# MC15.net
KiCad netlist of a schematic drawn in Altium Designer
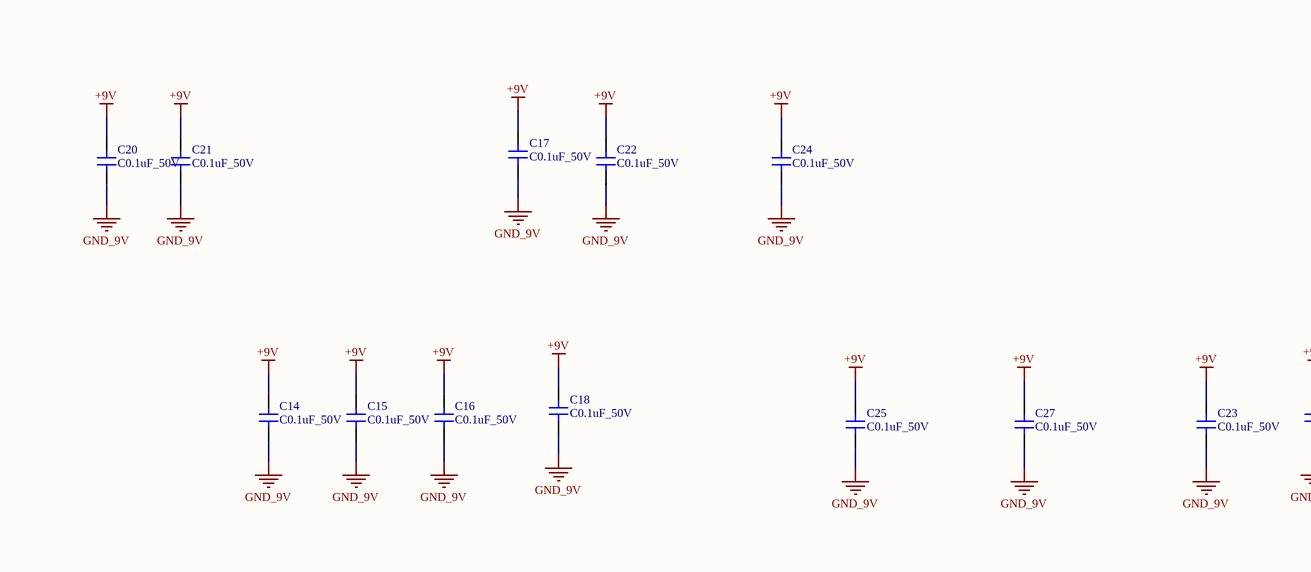
[diagram p0: MC15.SchDoc, top left]
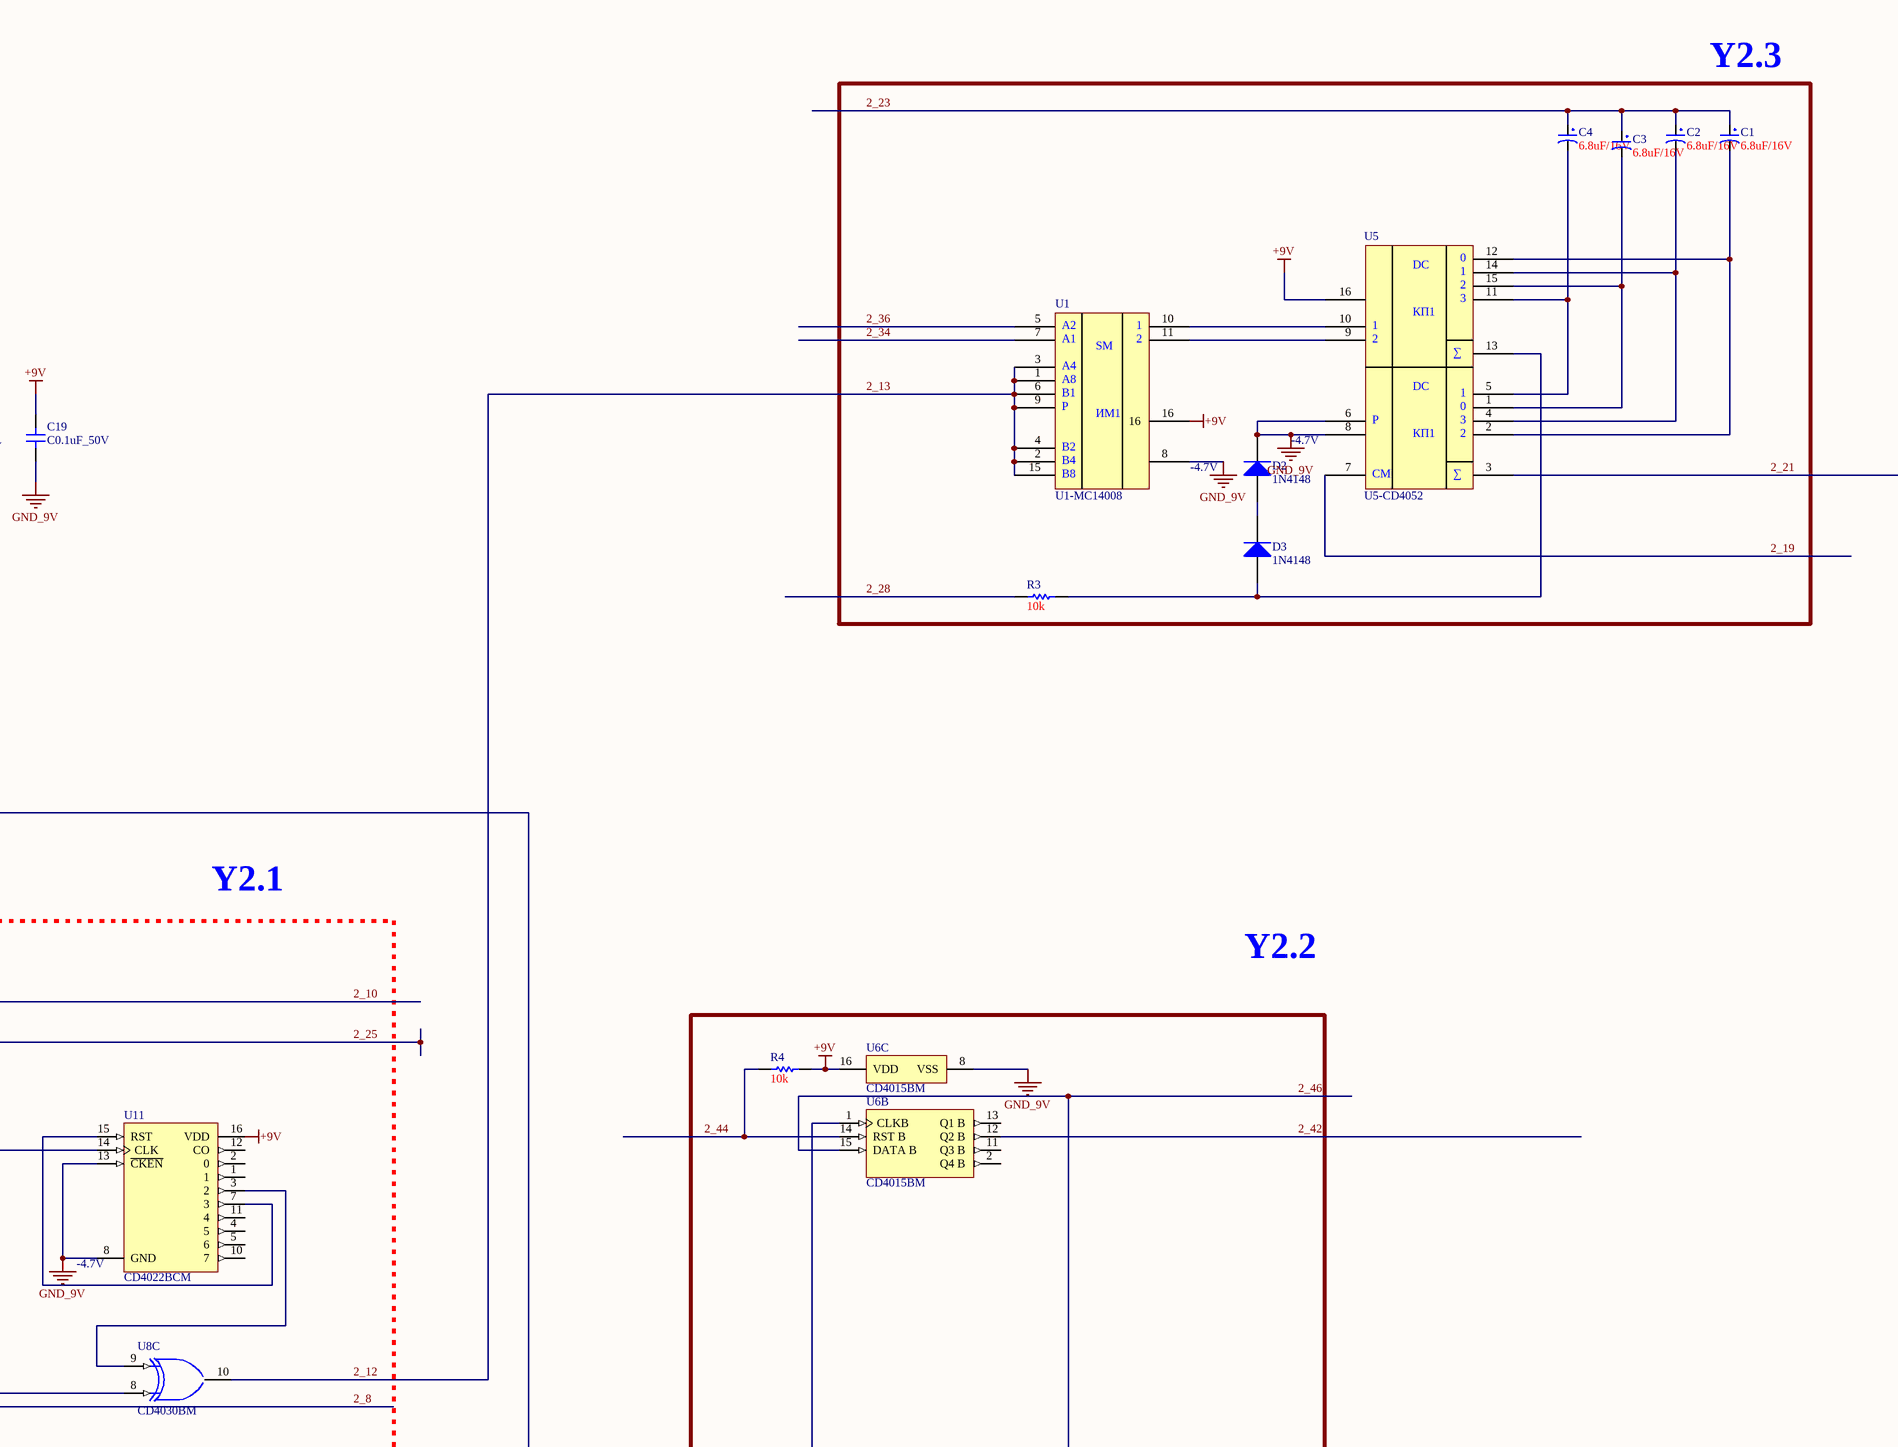
[diagram p1: MC15.SchDoc, top right]
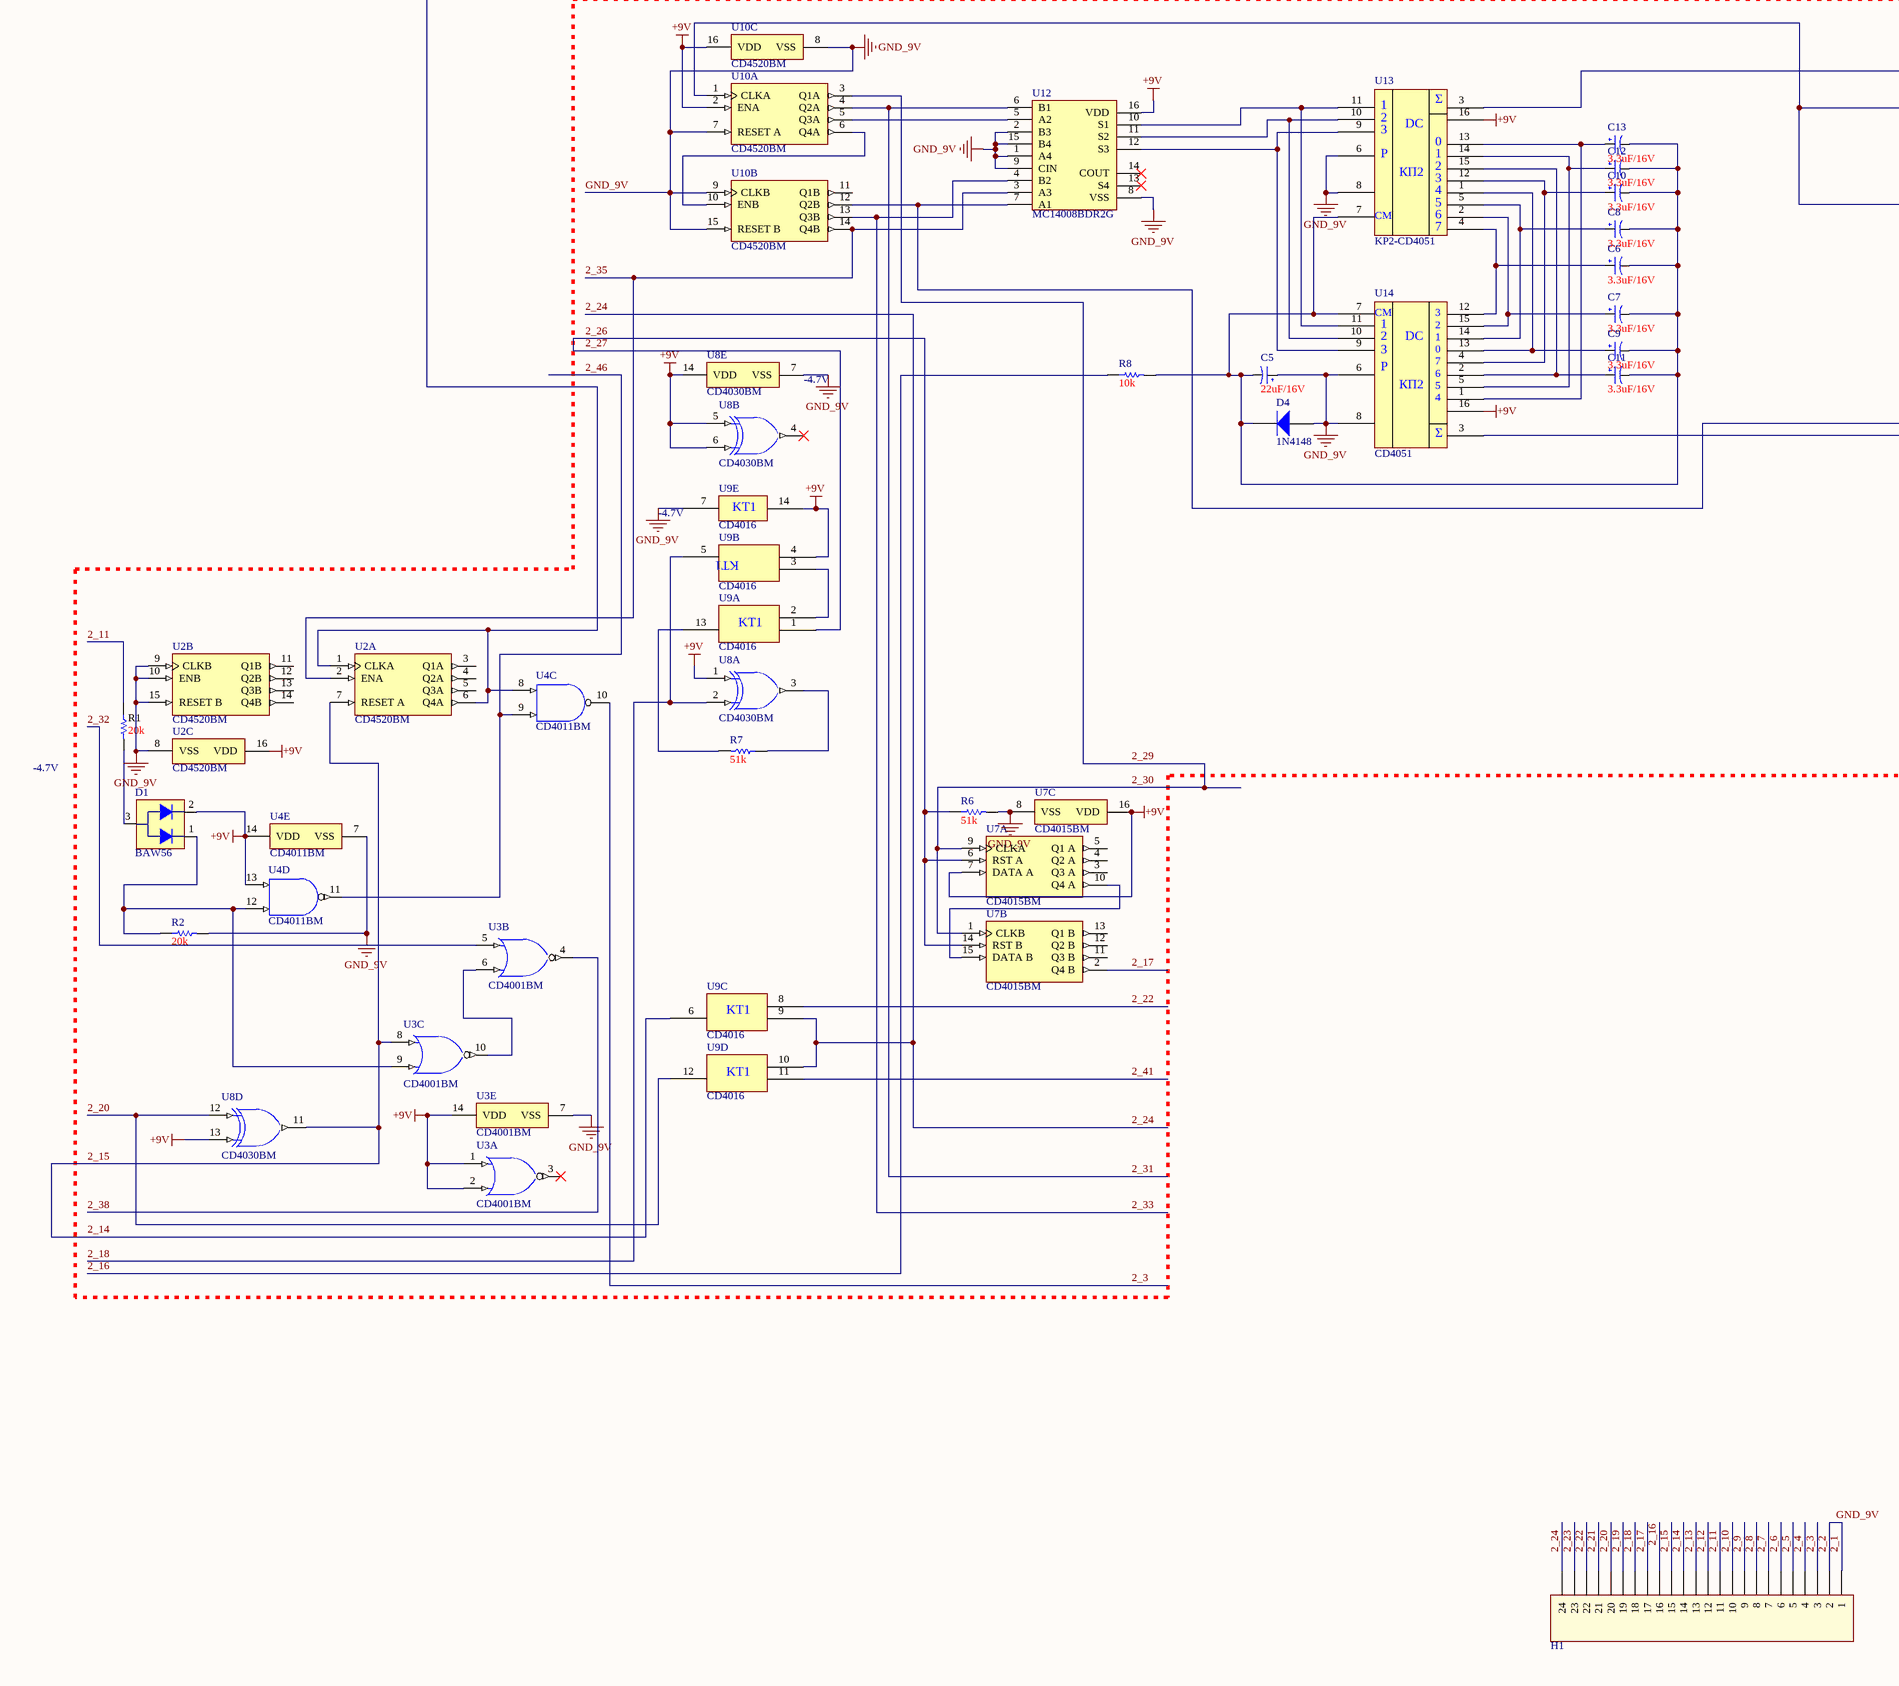
[diagram p2: MC15.SchDoc, bottom left]
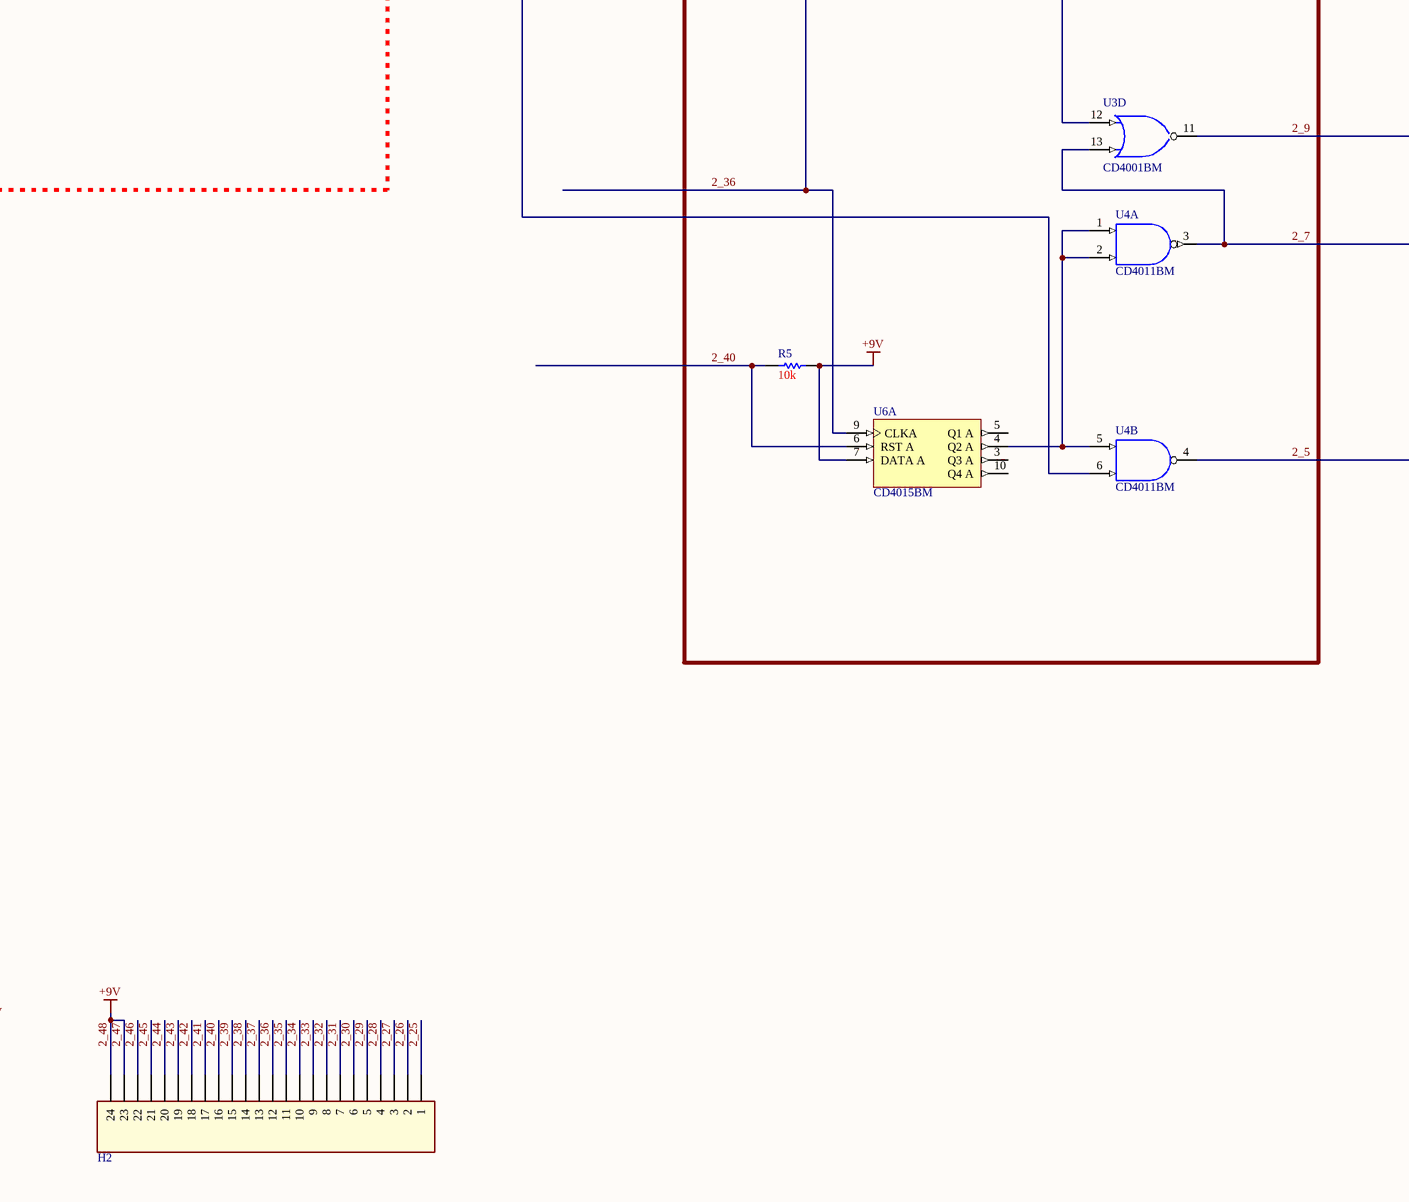
[diagram p3: MC15.SchDoc, bottom right]

(export (version "E")
  (design (tool "Eeschema 10.0.6"))
  (components
    (comp (ref "C1")
      (value "6.8uF/16V")
      (footprint "3216")
      (description "C 47uF/50V , 220uF/16V")
      (libsource (lib "syhaunguyen") (part "CP2"))
    )
    (comp (ref "C2")
      (value "6.8uF/16V")
      (footprint "3216")
      (description "C 47uF/50V , 220uF/16V")
      (libsource (lib "syhaunguyen") (part "CP2"))
    )
    (comp (ref "C3")
      (value "6.8uF/16V")
      (footprint "3216")
      (description "C 47uF/50V , 220uF/16V")
      (libsource (lib "syhaunguyen") (part "CP2"))
    )
    (comp (ref "C4")
      (value "6.8uF/16V")
      (footprint "3216")
      (description "C 47uF/50V , 220uF/16V")
      (libsource (lib "syhaunguyen") (part "CP2"))
    )
    (comp (ref "C5")
      (value "22uF/16V")
      (footprint "3528")
      (description "Cap P  0,1uF < 22uF , 16 - 50V")
      (libsource (lib "syhaunguyen") (part "CP1"))
    )
    (comp (ref "C6")
      (value "3.3uF/16V")
      (footprint "3216")
      (description "Cap P  0,1uF < 22uF , 16 - 50V")
      (libsource (lib "syhaunguyen") (part "CP1"))
    )
    (comp (ref "C7")
      (value "3.3uF/16V")
      (footprint "3216")
      (description "Cap P  0,1uF < 22uF , 16 - 50V")
      (libsource (lib "syhaunguyen") (part "CP1"))
    )
    (comp (ref "C8")
      (value "3.3uF/16V")
      (footprint "3216")
      (description "Cap P  0,1uF < 22uF , 16 - 50V")
      (libsource (lib "syhaunguyen") (part "CP1"))
    )
    (comp (ref "C9")
      (value "3.3uF/16V")
      (footprint "3216")
      (description "Cap P  0,1uF < 22uF , 16 - 50V")
      (libsource (lib "syhaunguyen") (part "CP1"))
    )
    (comp (ref "C10")
      (value "3.3uF/16V")
      (footprint "3216")
      (description "Cap P  0,1uF < 22uF , 16 - 50V")
      (libsource (lib "syhaunguyen") (part "CP1"))
    )
    (comp (ref "C11")
      (value "3.3uF/16V")
      (footprint "3216")
      (description "Cap P  0,1uF < 22uF , 16 - 50V")
      (libsource (lib "syhaunguyen") (part "CP1"))
    )
    (comp (ref "C12")
      (value "3.3uF/16V")
      (footprint "3216")
      (description "Cap P  0,1uF < 22uF , 16 - 50V")
      (libsource (lib "syhaunguyen") (part "CP1"))
    )
    (comp (ref "C13")
      (value "3.3uF/16V")
      (footprint "3216")
      (description "Cap P  0,1uF < 22uF , 16 - 50V")
      (libsource (lib "syhaunguyen") (part "CP1"))
    )
    (comp (ref "C14")
      (value "C0.1uF_50V")
      (footprint "Masterit1805:C0805")
      (libsource (lib "AMK") (part "C0.1uF_50V"))
    )
    (comp (ref "C15")
      (value "C0.1uF_50V")
      (footprint "Masterit1805:C0805")
      (libsource (lib "AMK") (part "C0.1uF_50V"))
    )
    (comp (ref "C16")
      (value "C0.1uF_50V")
      (footprint "Masterit1805:C0805")
      (libsource (lib "AMK") (part "C0.1uF_50V"))
    )
    (comp (ref "C17")
      (value "C0.1uF_50V")
      (footprint "Masterit1805:C0805")
      (libsource (lib "AMK") (part "C0.1uF_50V"))
    )
    (comp (ref "C18")
      (value "C0.1uF_50V")
      (footprint "Masterit1805:C0805")
      (libsource (lib "AMK") (part "C0.1uF_50V"))
    )
    (comp (ref "C19")
      (value "C0.1uF_50V")
      (footprint "Masterit1805:C0805")
      (libsource (lib "AMK") (part "C0.1uF_50V"))
    )
    (comp (ref "C20")
      (value "C0.1uF_50V")
      (footprint "Masterit1805:C0805")
      (libsource (lib "AMK") (part "C0.1uF_50V"))
    )
    (comp (ref "C21")
      (value "C0.1uF_50V")
      (footprint "Masterit1805:C0805")
      (libsource (lib "AMK") (part "C0.1uF_50V"))
    )
    (comp (ref "C22")
      (value "C0.1uF_50V")
      (footprint "Masterit1805:C0805")
      (libsource (lib "AMK") (part "C0.1uF_50V"))
    )
    (comp (ref "C23")
      (value "C0.1uF_50V")
      (footprint "Masterit1805:C0805")
      (libsource (lib "AMK") (part "C0.1uF_50V"))
    )
    (comp (ref "C24")
      (value "C0.1uF_50V")
      (footprint "Masterit1805:C0805")
      (libsource (lib "AMK") (part "C0.1uF_50V"))
    )
    (comp (ref "C25")
      (value "C0.1uF_50V")
      (footprint "Masterit1805:C0805")
      (libsource (lib "AMK") (part "C0.1uF_50V"))
    )
    (comp (ref "C27")
      (value "C0.1uF_50V")
      (footprint "Masterit1805:C0805")
      (libsource (lib "AMK") (part "C0.1uF_50V"))
    )
    (comp (ref "D1") (value "BAW56") (footprint "sot-23") (libsource (lib "27V-30A") (part "UF3")))
    (comp (ref "D2")
      (value "1N4148")
      (footprint "SOD123")
      (description "Dán")
      (libsource (lib "Altium_Lib_by_KhueNguyenCreator") (part "Diode S4"))
    )
    (comp (ref "D3")
      (value "1N4148")
      (footprint "SOD123")
      (description "Dán")
      (libsource (lib "Altium_Lib_by_KhueNguyenCreator") (part "Diode S4"))
    )
    (comp (ref "D4")
      (value "1N4148")
      (footprint "SOD123")
      (description "Dán")
      (libsource (lib "Altium_Lib_by_KhueNguyenCreator") (part "Diode S4"))
    )
    (comp (ref "H1")
      (value "Header 24")
      (footprint "header 24")
      (libsource (lib "LIB_EMBEDDED1805") (part "Header 24"))
    )
    (comp (ref "H2")
      (value "Header 24")
      (footprint "header 24")
      (libsource (lib "LIB_EMBEDDED1805") (part "Header 24"))
    )
    (comp (ref "R1")
      (value "20k")
      (footprint "R0805")
      (description "Standard resistor")
      (fields (field (name "ASID PART NUMBER") "Res-AS"))
      (libsource (lib "Mylib+Rev+4") (part "Res"))
    )
    (comp (ref "R2")
      (value "20k")
      (footprint "R0805")
      (description "Standard resistor")
      (fields (field (name "ASID PART NUMBER") "Res-AS"))
      (libsource (lib "Mylib+Rev+4") (part "Res"))
    )
    (comp (ref "R3")
      (value "10k")
      (footprint "Masterit1805:C0805")
      (description "Standard resistor")
      (fields (field (name "ASID PART NUMBER") "Res-AS"))
      (libsource (lib "Mylib+Rev+4") (part "Res"))
    )
    (comp (ref "R4")
      (value "10k")
      (footprint "R0805")
      (description "Standard resistor")
      (fields (field (name "ASID PART NUMBER") "Res-AS"))
      (libsource (lib "Mylib+Rev+4") (part "Res"))
    )
    (comp (ref "R5")
      (value "10k")
      (footprint "R0805")
      (description "Standard resistor")
      (fields (field (name "ASID PART NUMBER") "Res-AS"))
      (libsource (lib "Mylib+Rev+4") (part "Res"))
    )
    (comp (ref "R6")
      (value "51k")
      (footprint "R0805")
      (description "Standard resistor")
      (fields (field (name "ASID PART NUMBER") "Res-AS"))
      (libsource (lib "Mylib+Rev+4") (part "Res"))
    )
    (comp (ref "R7")
      (value "51k")
      (footprint "Masterit1805:C0805")
      (description "Standard resistor")
      (fields (field (name "ASID PART NUMBER") "Res-AS"))
      (libsource (lib "Mylib+Rev+4") (part "Res"))
    )
    (comp (ref "R8")
      (value "10k")
      (footprint "R0805")
      (description "Standard resistor")
      (fields (field (name "ASID PART NUMBER") "Res-AS"))
      (libsource (lib "Mylib+Rev+4") (part "Res"))
    )
    (comp (ref "U1")
      (value "U1-MC14008")
      (footprint "soic16n")
      (libsource (lib "LIB_OF_PHONG") (part "U1-MC14008"))
    )
    (comp (ref "U2")
      (value "CD4520BM")
      (footprint "D0016A_N")
      (description "CMOS Dual Binary Up-Counter, D0016A, TUBE")
      (fields
        (field (name "GENERIC PART NUMBER") "CD4520B")
        (field (name "MANUFACTURER") "Texas Instruments")
      )
      (libsource (lib "TI_Logic_Specialty_Logic") (part "CD4520BM"))
    )
    (comp (ref "U3")
      (value "CD4001BM")
      (footprint "D0014A_N")
      (description "CMOS Quad 2-Input NOR Gate, D0014A, TUBE")
      (fields
        (field (name "GENERIC PART NUMBER") "CD4001B")
        (field (name "MANUFACTURER") "Texas Instruments")
      )
      (libsource (lib "TI_Logic_Gate") (part "CD4001BM"))
    )
    (comp (ref "U4")
      (value "CD4011BM")
      (footprint "D0014A_N")
      (description "CMOS Quad 2-Input NAND Gate, D0014A, TUBE")
      (fields
        (field (name "GENERIC PART NUMBER") "CD4011B")
        (field (name "MANUFACTURER") "Texas Instruments")
      )
      (libsource (lib "TI_Logic_Gate") (part "CD4011BM"))
    )
    (comp (ref "U5")
      (value "U5-CD4052")
      (footprint "soic16n")
      (libsource (lib "LIB_OF_PHONG") (part "U5-CD4052"))
    )
    (comp (ref "U6")
      (value "CD4015BM")
      (footprint "D0016A_N")
      (description "CMOS Dual 4-Stage Static Shift Register, D0016A, TUBE")
      (fields
        (field (name "GENERIC PART NUMBER") "CD4015B")
        (field (name "MANUFACTURER") "Texas Instruments")
      )
      (libsource (lib "TI_Logic_Flip-Flop,Latch,Register") (part "CD4015BM"))
    )
    (comp (ref "U7")
      (value "CD4015BM")
      (footprint "D0016A_N")
      (description "CMOS Dual 4-Stage Static Shift Register, D0016A, TUBE")
      (fields
        (field (name "GENERIC PART NUMBER") "CD4015B")
        (field (name "MANUFACTURER") "Texas Instruments")
      )
      (libsource (lib "TI_Logic_Flip-Flop,Latch,Register") (part "CD4015BM"))
    )
    (comp (ref "U8")
      (value "CD4030BM")
      (footprint "D0014A_N")
      (description "CMOS Quad Exclusive-OR Gate, D0014A, TUBE")
      (fields
        (field (name "GENERIC PART NUMBER") "CD4030B")
        (field (name "MANUFACTURER") "Texas Instruments")
      )
      (libsource (lib "TI_Logic_Gate") (part "CD4030BM"))
    )
    (comp (ref "U9") (value "CD4016") (footprint "SOIC14") (libsource (lib "LIB_OF_PHONG") (part "CD4016")))
    (comp (ref "U10")
      (value "CD4520BM")
      (footprint "D0016A_N")
      (description "CMOS Dual Binary Up-Counter, D0016A, TUBE")
      (fields
        (field (name "GENERIC PART NUMBER") "CD4520B")
        (field (name "MANUFACTURER") "Texas Instruments")
      )
      (libsource (lib "TI_Logic_Specialty_Logic") (part "CD4520BM"))
    )
    (comp (ref "U11")
      (value "CD4022BCM")
      (footprint "SOP16")
      (description "Divide by 8 Counter/Divider with 8 Decoded Outputs")
      (fields (field (name "PUBLISHER") "Altium Limited"))
      (libsource (lib "FSC Logic Counter") (part "CD4022BCM"))
    )
    (comp (ref "U12")
      (value "MC14008BDR2G")
      (footprint "SamacSys:SOIC127P600X175-16N")
      (description "THAY THẾ CD4008")
      (fields (field (name "MOUSER PART NUMBER") "863-MC14008BDR2G"))
      (libsource (lib "*") (part "MC14008BDR2G"))
    )
    (comp (ref "U13")
      (value "KP2-CD4051")
      (footprint "soic16n")
      (libsource (lib "LIB_OF_PHONG") (part "KP2-CD4051"))
    )
    (comp (ref "U14") (value "CD4051") (footprint "soic16n") (libsource (lib "LIB_OF_PHONG") (part "CD4051")))
  )
  (nets
    (net (code "1") (name "+9V") (class "Default")
      (node (ref "C14") (pin "2") (pinfunction "2_2") (pintype "passive"))
      (node (ref "C15") (pin "2") (pinfunction "2_2") (pintype "passive"))
      (node (ref "C16") (pin "2") (pinfunction "2_2") (pintype "passive"))
      (node (ref "C17") (pin "2") (pinfunction "2_2") (pintype "passive"))
      (node (ref "C18") (pin "2") (pinfunction "2_2") (pintype "passive"))
      (node (ref "C19") (pin "2") (pinfunction "2_2") (pintype "passive"))
      (node (ref "C20") (pin "2") (pinfunction "2_2") (pintype "passive"))
      (node (ref "C21") (pin "2") (pinfunction "2_2") (pintype "passive"))
      (node (ref "C22") (pin "2") (pinfunction "2_2") (pintype "passive"))
      (node (ref "C23") (pin "2") (pinfunction "2_2") (pintype "passive"))
      (node (ref "C24") (pin "2") (pinfunction "2_2") (pintype "passive"))
      (node (ref "C25") (pin "2") (pinfunction "2_2") (pintype "passive"))
      (node (ref "C27") (pin "2") (pinfunction "2_2") (pintype "passive"))
      (node (ref "D1") (pin "2") (pinfunction "2_2") (pintype "passive"))
      (node (ref "H2") (pin "23") (pinfunction "23_23") (pintype "passive"))
      (node (ref "H2") (pin "24") (pinfunction "24_24") (pintype "passive"))
      (node (ref "R4") (pin "2") (pinfunction "2_2") (pintype "passive"))
      (node (ref "R5") (pin "1") (pinfunction "1_1") (pintype "passive"))
      (node (ref "U1") (pin "16") (pinfunction "16_16") (pintype "passive"))
      (node (ref "U10") (pin "16") (pinfunction "VDD_16") (pintype "power_in"))
      (node (ref "U10") (pin "2") (pinfunction "ENA_2") (pintype "input"))
      (node (ref "U11") (pin "16") (pinfunction "VDD_16") (pintype "power_in"))
      (node (ref "U12") (pin "16") (pinfunction "VDD_16") (pintype "passive"))
      (node (ref "U13") (pin "16") (pinfunction "16_16") (pintype "passive"))
      (node (ref "U14") (pin "16") (pinfunction "16_16") (pintype "passive"))
      (node (ref "U2") (pin "16") (pinfunction "VDD_16") (pintype "power_in"))
      (node (ref "U3") (pin "1") (pinfunction "A_1") (pintype "input"))
      (node (ref "U3") (pin "14") (pinfunction "VDD_14") (pintype "power_in"))
      (node (ref "U3") (pin "2") (pinfunction "B_2") (pintype "input"))
      (node (ref "U4") (pin "13") (pinfunction "H_13") (pintype "input"))
      (node (ref "U4") (pin "14") (pinfunction "VDD_14") (pintype "power_in"))
      (node (ref "U5") (pin "16") (pinfunction "16_16") (pintype "passive"))
      (node (ref "U6") (pin "16") (pinfunction "VDD_16") (pintype "power_in"))
      (node (ref "U6") (pin "7") (pinfunction "DATA_A_7") (pintype "input"))
      (node (ref "U7") (pin "16") (pinfunction "VDD_16") (pintype "power_in"))
      (node (ref "U7") (pin "7") (pinfunction "DATA_A_7") (pintype "input"))
      (node (ref "U8") (pin "1") (pinfunction "A_1") (pintype "input"))
      (node (ref "U8") (pin "13") (pinfunction "H_13") (pintype "input"))
      (node (ref "U8") (pin "14") (pinfunction "VDD_14") (pintype "power_in"))
      (node (ref "U8") (pin "5") (pinfunction "C_5") (pintype "input"))
      (node (ref "U8") (pin "6") (pinfunction "D_6") (pintype "input"))
      (node (ref "U9") (pin "14") (pinfunction "14_14") (pintype "passive"))
      (node (ref "U9") (pin "4") (pinfunction "4_4") (pintype "passive"))
    )
    (net (code "2") (name "/2_3") (class "Default")
      (node (ref "H1") (pin "3") (pinfunction "3_3") (pintype "passive"))
      (node (ref "U4") (pin "10") (pinfunction "L_10") (pintype "passive"))
    )
    (net (code "3") (name "/2_4") (class "Default")
      (node (ref "H1") (pin "4") (pinfunction "4_4") (pintype "passive"))
    )
    (net (code "4") (name "/2_5") (class "Default")
      (node (ref "H1") (pin "5") (pinfunction "5_5") (pintype "passive"))
      (node (ref "U4") (pin "4") (pinfunction "K_4") (pintype "output"))
    )
    (net (code "5") (name "/2_6") (class "Default")
      (node (ref "H1") (pin "6") (pinfunction "6_6") (pintype "passive"))
    )
    (net (code "6") (name "/2_7") (class "Default")
      (node (ref "H1") (pin "7") (pinfunction "7_7") (pintype "passive"))
      (node (ref "U3") (pin "13") (pinfunction "H_13") (pintype "input"))
      (node (ref "U4") (pin "3") (pinfunction "J_3") (pintype "output"))
    )
    (net (code "7") (name "/2_8") (class "Default")
      (node (ref "H1") (pin "8") (pinfunction "8_8") (pintype "passive"))
      (node (ref "U14") (pin "3") (pinfunction "3_3") (pintype "passive"))
    )
    (net (code "8") (name "/2_9") (class "Default")
      (node (ref "H1") (pin "9") (pinfunction "9_9") (pintype "passive"))
      (node (ref "U3") (pin "11") (pinfunction "M_11") (pintype "output"))
    )
    (net (code "9") (name "/2_10") (class "Default")
      (node (ref "H1") (pin "10") (pinfunction "10_10") (pintype "passive"))
      (node (ref "U13") (pin "3") (pinfunction "3_3") (pintype "passive"))
    )
    (net (code "10") (name "/2_11") (class "Default")
      (node (ref "H1") (pin "11") (pinfunction "11_11") (pintype "passive"))
      (node (ref "R1") (pin "1") (pinfunction "1_1") (pintype "passive"))
    )
    (net (code "11") (name "/2_12") (class "Default")
      (node (ref "H1") (pin "12") (pinfunction "12_12") (pintype "passive"))
      (node (ref "H1") (pin "13") (pinfunction "13_13") (pintype "passive"))
      (node (ref "U1") (pin "1") (pinfunction "1_1") (pintype "passive"))
      (node (ref "U1") (pin "15") (pinfunction "15_15") (pintype "passive"))
      (node (ref "U1") (pin "2") (pinfunction "2_2") (pintype "passive"))
      (node (ref "U1") (pin "3") (pinfunction "3_3") (pintype "passive"))
      (node (ref "U1") (pin "4") (pinfunction "4_4") (pintype "passive"))
      (node (ref "U1") (pin "6") (pinfunction "6_6") (pintype "passive"))
      (node (ref "U1") (pin "9") (pinfunction "9_9") (pintype "passive"))
      (node (ref "U8") (pin "10") (pinfunction "L_10") (pintype "passive"))
    )
    (net (code "12") (name "/2_14") (class "Default")
      (node (ref "H1") (pin "14") (pinfunction "14_14") (pintype "passive"))
      (node (ref "H1") (pin "15") (pinfunction "15_15") (pintype "passive"))
      (node (ref "U2") (pin "7") (pinfunction "RESET_A_7") (pintype "input"))
      (node (ref "U3") (pin "8") (pinfunction "E_8") (pintype "input"))
      (node (ref "U8") (pin "11") (pinfunction "M_11") (pintype "output"))
      (node (ref "U9") (pin "6") (pinfunction "6_6") (pintype "passive"))
    )
    (net (code "13") (name "/2_16") (class "Default")
      (node (ref "H1") (pin "16") (pinfunction "16_16") (pintype "passive"))
      (node (ref "R8") (pin "1") (pinfunction "1_1") (pintype "passive"))
    )
    (net (code "14") (name "/2_17") (class "Default")
      (node (ref "H1") (pin "17") (pinfunction "17_17") (pintype "passive"))
      (node (ref "U7") (pin "2") (pinfunction "Q4_B_2") (pintype "output"))
    )
    (net (code "15") (name "/2_18") (class "Default")
      (node (ref "H1") (pin "18") (pinfunction "18_18") (pintype "passive"))
      (node (ref "U8") (pin "2") (pinfunction "B_2") (pintype "input"))
      (node (ref "U9") (pin "5") (pinfunction "5_5") (pintype "passive"))
    )
    (net (code "16") (name "/2_19") (class "Default")
      (node (ref "H1") (pin "19") (pinfunction "19_19") (pintype "passive"))
      (node (ref "U5") (pin "7") (pinfunction "7_7") (pintype "passive"))
    )
    (net (code "17") (name "/2_20") (class "Default")
      (node (ref "H1") (pin "20") (pinfunction "20_20") (pintype "passive"))
      (node (ref "U8") (pin "12") (pinfunction "G_12") (pintype "input"))
      (node (ref "U9") (pin "12") (pinfunction "12_12") (pintype "passive"))
    )
    (net (code "18") (name "/2_21") (class "Default")
      (node (ref "H1") (pin "21") (pinfunction "21_21") (pintype "passive"))
      (node (ref "U5") (pin "3") (pinfunction "3_3") (pintype "passive"))
    )
    (net (code "19") (name "/2_22") (class "Default")
      (node (ref "H1") (pin "22") (pinfunction "22_22") (pintype "passive"))
      (node (ref "U9") (pin "8") (pinfunction "8_8") (pintype "passive"))
    )
    (net (code "20") (name "/2_23") (class "Default")
      (node (ref "C1") (pin "1") (pinfunction "1_1") (pintype "passive"))
      (node (ref "C2") (pin "1") (pinfunction "1_1") (pintype "passive"))
      (node (ref "C3") (pin "1") (pinfunction "1_1") (pintype "passive"))
      (node (ref "C4") (pin "1") (pinfunction "1_1") (pintype "passive"))
      (node (ref "H1") (pin "23") (pinfunction "23_23") (pintype "passive"))
    )
    (net (code "21") (name "/2_24") (class "Default")
      (node (ref "H1") (pin "24") (pinfunction "24_24") (pintype "passive"))
      (node (ref "U9") (pin "10") (pinfunction "10_10") (pintype "passive"))
      (node (ref "U9") (pin "9") (pinfunction "9_9") (pintype "passive"))
    )
    (net (code "22") (name "/2_25") (class "Default")
      (node (ref "H2") (pin "1") (pinfunction "1_1") (pintype "passive"))
      (node (ref "U10") (pin "1") (pinfunction "CLKA_1") (pintype "input"))
      (node (ref "U11") (pin "14") (pinfunction "CLK_14") (pintype "input"))
    )
    (net (code "23") (name "/2_26") (class "Default")
      (node (ref "H2") (pin "2") (pinfunction "2_2") (pintype "passive"))
      (node (ref "H2") (pin "3") (pinfunction "3_3") (pintype "passive"))
      (node (ref "R6") (pin "1") (pinfunction "1_1") (pintype "passive"))
      (node (ref "U7") (pin "14") (pinfunction "RST_B_14") (pintype "input"))
      (node (ref "U7") (pin "6") (pinfunction "RST_A_6") (pintype "input"))
      (node (ref "U9") (pin "1") (pinfunction "1_1") (pintype "passive"))
    )
    (net (code "24") (name "/2_28") (class "Default")
      (node (ref "H2") (pin "4") (pinfunction "4_4") (pintype "passive"))
      (node (ref "R3") (pin "2") (pinfunction "2_2") (pintype "passive"))
    )
    (net (code "25") (name "/2_29") (class "Default")
      (node (ref "H2") (pin "5") (pinfunction "5_5") (pintype "passive"))
      (node (ref "H2") (pin "6") (pinfunction "6_6") (pintype "passive"))
      (node (ref "U10") (pin "3") (pinfunction "Q1A_3") (pintype "output"))
      (node (ref "U7") (pin "1") (pinfunction "CLKB_1") (pintype "input"))
      (node (ref "U7") (pin "9") (pinfunction "CLKA_9") (pintype "input"))
    )
    (net (code "26") (name "/2_31") (class "Default")
      (node (ref "H2") (pin "7") (pinfunction "7_7") (pintype "passive"))
      (node (ref "U10") (pin "4") (pinfunction "Q2A_4") (pintype "output"))
      (node (ref "U12") (pin "6") (pinfunction "B1_6") (pintype "passive"))
    )
    (net (code "27") (name "/2_32") (class "Default")
      (node (ref "H2") (pin "8") (pinfunction "8_8") (pintype "passive"))
      (node (ref "U3") (pin "5") (pinfunction "C_5") (pintype "input"))
    )
    (net (code "28") (name "/2_33") (class "Default")
      (node (ref "H2") (pin "9") (pinfunction "9_9") (pintype "passive"))
      (node (ref "U10") (pin "13") (pinfunction "Q3B_13") (pintype "output"))
      (node (ref "U12") (pin "4") (pinfunction "B2_4") (pintype "passive"))
    )
    (net (code "29") (name "/2_34") (class "Default")
      (node (ref "H2") (pin "10") (pinfunction "10_10") (pintype "passive"))
      (node (ref "U1") (pin "7") (pinfunction "7_7") (pintype "passive"))
    )
    (net (code "30") (name "/2_35") (class "Default")
      (node (ref "H2") (pin "11") (pinfunction "11_11") (pintype "passive"))
      (node (ref "U10") (pin "14") (pinfunction "Q4B_14") (pintype "output"))
      (node (ref "U12") (pin "3") (pinfunction "A3_3") (pintype "passive"))
      (node (ref "U2") (pin "2") (pinfunction "ENA_2") (pintype "input"))
    )
    (net (code "31") (name "/2_36") (class "Default")
      (node (ref "H2") (pin "12") (pinfunction "12_12") (pintype "passive"))
      (node (ref "U1") (pin "5") (pinfunction "5_5") (pintype "passive"))
      (node (ref "U6") (pin "1") (pinfunction "CLKB_1") (pintype "input"))
      (node (ref "U6") (pin "9") (pinfunction "CLKA_9") (pintype "input"))
    )
    (net (code "32") (name "/2_37") (class "Default")
      (node (ref "H2") (pin "13") (pinfunction "13_13") (pintype "passive"))
    )
    (net (code "33") (name "/2_38") (class "Default")
      (node (ref "H2") (pin "14") (pinfunction "14_14") (pintype "passive"))
      (node (ref "U3") (pin "4") (pinfunction "K_4") (pintype "output"))
    )
    (net (code "34") (name "/2_39") (class "Default")
      (node (ref "H2") (pin "15") (pinfunction "15_15") (pintype "passive"))
    )
    (net (code "35") (name "/2_40") (class "Default")
      (node (ref "H2") (pin "16") (pinfunction "16_16") (pintype "passive"))
      (node (ref "R5") (pin "2") (pinfunction "2_2") (pintype "passive"))
      (node (ref "U6") (pin "6") (pinfunction "RST_A_6") (pintype "input"))
    )
    (net (code "36") (name "/2_41") (class "Default")
      (node (ref "H2") (pin "17") (pinfunction "17_17") (pintype "passive"))
      (node (ref "U9") (pin "11") (pinfunction "11_11") (pintype "passive"))
    )
    (net (code "37") (name "/2_42") (class "Default")
      (node (ref "H2") (pin "18") (pinfunction "18_18") (pintype "passive"))
      (node (ref "U6") (pin "12") (pinfunction "Q2_B_12") (pintype "output"))
    )
    (net (code "38") (name "/2_43") (class "Default")
      (node (ref "H2") (pin "19") (pinfunction "19_19") (pintype "passive"))
    )
    (net (code "39") (name "/2_44") (class "Default")
      (node (ref "H2") (pin "20") (pinfunction "20_20") (pintype "passive"))
      (node (ref "R4") (pin "1") (pinfunction "1_1") (pintype "passive"))
      (node (ref "U6") (pin "14") (pinfunction "RST_B_14") (pintype "input"))
    )
    (net (code "40") (name "/2_45") (class "Default")
      (node (ref "H2") (pin "21") (pinfunction "21_21") (pintype "passive"))
    )
    (net (code "41") (name "/2_46") (class "Default")
      (node (ref "H2") (pin "22") (pinfunction "22_22") (pintype "passive"))
      (node (ref "U3") (pin "12") (pinfunction "G_12") (pintype "input"))
      (node (ref "U4") (pin "11") (pinfunction "M_11") (pintype "output"))
      (node (ref "U4") (pin "9") (pinfunction "F_9") (pintype "input"))
      (node (ref "U6") (pin "15") (pinfunction "DATA_B_15") (pintype "input"))
    )
    (net (code "42") (name "GND_9V") (class "Default")
      (node (ref "C14") (pin "1") (pinfunction "1_1") (pintype "passive"))
      (node (ref "C15") (pin "1") (pinfunction "1_1") (pintype "passive"))
      (node (ref "C16") (pin "1") (pinfunction "1_1") (pintype "passive"))
      (node (ref "C17") (pin "1") (pinfunction "1_1") (pintype "passive"))
      (node (ref "C18") (pin "1") (pinfunction "1_1") (pintype "passive"))
      (node (ref "C19") (pin "1") (pinfunction "1_1") (pintype "passive"))
      (node (ref "C20") (pin "1") (pinfunction "1_1") (pintype "passive"))
      (node (ref "C21") (pin "1") (pinfunction "1_1") (pintype "passive"))
      (node (ref "C22") (pin "1") (pinfunction "1_1") (pintype "passive"))
      (node (ref "C23") (pin "1") (pinfunction "1_1") (pintype "passive"))
      (node (ref "C24") (pin "1") (pinfunction "1_1") (pintype "passive"))
      (node (ref "C25") (pin "1") (pinfunction "1_1") (pintype "passive"))
      (node (ref "C27") (pin "1") (pinfunction "1_1") (pintype "passive"))
      (node (ref "C5") (pin "1") (pinfunction "1_1") (pintype "passive"))
      (node (ref "D2") (pin "2") (pinfunction "K_2") (pintype "passive"))
      (node (ref "D4") (pin "1") (pinfunction "A_1") (pintype "passive"))
      (node (ref "H1") (pin "1") (pinfunction "1_1") (pintype "passive"))
      (node (ref "H1") (pin "2") (pinfunction "2_2") (pintype "passive"))
      (node (ref "R2") (pin "2") (pinfunction "2_2") (pintype "passive"))
      (node (ref "R6") (pin "2") (pinfunction "2_2") (pintype "passive"))
      (node (ref "U1") (pin "8") (pinfunction "8_8") (pintype "passive"))
      (node (ref "U10") (pin "15") (pinfunction "RESET_B_15") (pintype "input"))
      (node (ref "U10") (pin "7") (pinfunction "RESET_A_7") (pintype "input"))
      (node (ref "U10") (pin "8") (pinfunction "VSS_8") (pintype "power_in"))
      (node (ref "U10") (pin "9") (pinfunction "CLKB_9") (pintype "input"))
      (node (ref "U11") (pin "13") (pinfunction "~{CKEN}_13") (pintype "input"))
      (node (ref "U11") (pin "8") (pinfunction "GND_8") (pintype "power_in"))
      (node (ref "U12") (pin "1") (pinfunction "A4_1") (pintype "passive"))
      (node (ref "U12") (pin "15") (pinfunction "B4_15") (pintype "passive"))
      (node (ref "U12") (pin "2") (pinfunction "B3_2") (pintype "passive"))
      (node (ref "U12") (pin "8") (pinfunction "VSS_8") (pintype "passive"))
      (node (ref "U12") (pin "9") (pinfunction "CIN_9") (pintype "passive"))
      (node (ref "U13") (pin "6") (pinfunction "6_6") (pintype "passive"))
      (node (ref "U13") (pin "8") (pinfunction "8_8") (pintype "passive"))
      (node (ref "U14") (pin "6") (pinfunction "6_6") (pintype "passive"))
      (node (ref "U14") (pin "8") (pinfunction "8_8") (pintype "passive"))
      (node (ref "U2") (pin "10") (pinfunction "ENB_10") (pintype "input"))
      (node (ref "U2") (pin "15") (pinfunction "RESET_B_15") (pintype "input"))
      (node (ref "U2") (pin "8") (pinfunction "VSS_8") (pintype "power_in"))
      (node (ref "U2") (pin "9") (pinfunction "CLKB_9") (pintype "input"))
      (node (ref "U3") (pin "7") (pinfunction "VSS_7") (pintype "power_in"))
      (node (ref "U4") (pin "7") (pinfunction "VSS_7") (pintype "power_in"))
      (node (ref "U5") (pin "6") (pinfunction "6_6") (pintype "passive"))
      (node (ref "U5") (pin "8") (pinfunction "8_8") (pintype "passive"))
      (node (ref "U6") (pin "8") (pinfunction "VSS_8") (pintype "power_in"))
      (node (ref "U7") (pin "8") (pinfunction "VSS_8") (pintype "power_in"))
      (node (ref "U8") (pin "7") (pinfunction "VSS_7") (pintype "power_in"))
      (node (ref "U9") (pin "7") (pinfunction "7_7") (pintype "passive"))
    )
    (net (code "43") (name "Net-(C1-Pad2)") (class "Default")
      (node (ref "C1") (pin "2") (pinfunction "2_2") (pintype "passive"))
      (node (ref "U5") (pin "12") (pinfunction "12_12") (pintype "passive"))
      (node (ref "U5") (pin "2") (pinfunction "2_2") (pintype "passive"))
    )
    (net (code "44") (name "Net-(C2-Pad2)") (class "Default")
      (node (ref "C2") (pin "2") (pinfunction "2_2") (pintype "passive"))
      (node (ref "U5") (pin "14") (pinfunction "14_14") (pintype "passive"))
      (node (ref "U5") (pin "4") (pinfunction "4_4") (pintype "passive"))
    )
    (net (code "45") (name "Net-(C3-Pad2)") (class "Default")
      (node (ref "C3") (pin "2") (pinfunction "2_2") (pintype "passive"))
      (node (ref "U5") (pin "1") (pinfunction "1_1") (pintype "passive"))
      (node (ref "U5") (pin "15") (pinfunction "15_15") (pintype "passive"))
    )
    (net (code "46") (name "Net-(C4-Pad2)") (class "Default")
      (node (ref "C4") (pin "2") (pinfunction "2_2") (pintype "passive"))
      (node (ref "U5") (pin "11") (pinfunction "11_11") (pintype "passive"))
      (node (ref "U5") (pin "5") (pinfunction "5_5") (pintype "passive"))
    )
    (net (code "47") (name "Net-(C6-Pad1)") (class "Default")
      (node (ref "C6") (pin "1") (pinfunction "1_1") (pintype "passive"))
      (node (ref "U13") (pin "4") (pinfunction "4_4") (pintype "passive"))
      (node (ref "U14") (pin "12") (pinfunction "12_12") (pintype "passive"))
    )
    (net (code "48") (name "Net-(C7-Pad1)") (class "Default")
      (node (ref "C7") (pin "1") (pinfunction "1_1") (pintype "passive"))
      (node (ref "U13") (pin "2") (pinfunction "2_2") (pintype "passive"))
      (node (ref "U14") (pin "15") (pinfunction "15_15") (pintype "passive"))
    )
    (net (code "49") (name "Net-(C8-Pad1)") (class "Default")
      (node (ref "C8") (pin "1") (pinfunction "1_1") (pintype "passive"))
      (node (ref "U13") (pin "5") (pinfunction "5_5") (pintype "passive"))
      (node (ref "U14") (pin "14") (pinfunction "14_14") (pintype "passive"))
    )
    (net (code "50") (name "Net-(C9-Pad1)") (class "Default")
      (node (ref "C9") (pin "1") (pinfunction "1_1") (pintype "passive"))
      (node (ref "U13") (pin "1") (pinfunction "1_1") (pintype "passive"))
      (node (ref "U14") (pin "13") (pinfunction "13_13") (pintype "passive"))
    )
    (net (code "51") (name "Net-(C10-Pad1)") (class "Default")
      (node (ref "C10") (pin "1") (pinfunction "1_1") (pintype "passive"))
      (node (ref "U13") (pin "12") (pinfunction "12_12") (pintype "passive"))
      (node (ref "U14") (pin "4") (pinfunction "4_4") (pintype "passive"))
    )
    (net (code "52") (name "Net-(C11-Pad1)") (class "Default")
      (node (ref "C11") (pin "1") (pinfunction "1_1") (pintype "passive"))
      (node (ref "U13") (pin "15") (pinfunction "15_15") (pintype "passive"))
      (node (ref "U14") (pin "2") (pinfunction "2_2") (pintype "passive"))
    )
    (net (code "53") (name "Net-(C12-Pad1)") (class "Default")
      (node (ref "C12") (pin "1") (pinfunction "1_1") (pintype "passive"))
      (node (ref "U13") (pin "14") (pinfunction "14_14") (pintype "passive"))
      (node (ref "U14") (pin "5") (pinfunction "5_5") (pintype "passive"))
    )
    (net (code "54") (name "Net-(C13-Pad1)") (class "Default")
      (node (ref "C13") (pin "1") (pinfunction "1_1") (pintype "passive"))
      (node (ref "U13") (pin "13") (pinfunction "13_13") (pintype "passive"))
      (node (ref "U14") (pin "1") (pinfunction "1_1") (pintype "passive"))
    )
    (net (code "55") (name "Net-(D1-Pad3)") (class "Default")
      (node (ref "D1") (pin "3") (pinfunction "3_3") (pintype "passive"))
      (node (ref "R1") (pin "2") (pinfunction "2_2") (pintype "passive"))
    )
    (net (code "56") (name "Net-(D2-A)") (class "Default")
      (node (ref "D2") (pin "1") (pinfunction "A_1") (pintype "passive"))
      (node (ref "D3") (pin "2") (pinfunction "K_2") (pintype "passive"))
    )
    (net (code "57") (name "Net-(D3-A)") (class "Default")
      (node (ref "D3") (pin "1") (pinfunction "A_1") (pintype "passive"))
      (node (ref "R3") (pin "1") (pinfunction "1_1") (pintype "passive"))
      (node (ref "U5") (pin "13") (pinfunction "13_13") (pintype "passive"))
    )
    (net (code "58") (name "Net-(D4-K)") (class "Default")
      (node (ref "C10") (pin "2") (pinfunction "2_2") (pintype "passive"))
      (node (ref "C11") (pin "2") (pinfunction "2_2") (pintype "passive"))
      (node (ref "C12") (pin "2") (pinfunction "2_2") (pintype "passive"))
      (node (ref "C13") (pin "2") (pinfunction "2_2") (pintype "passive"))
      (node (ref "C5") (pin "2") (pinfunction "2_2") (pintype "passive"))
      (node (ref "C6") (pin "2") (pinfunction "2_2") (pintype "passive"))
      (node (ref "C7") (pin "2") (pinfunction "2_2") (pintype "passive"))
      (node (ref "C8") (pin "2") (pinfunction "2_2") (pintype "passive"))
      (node (ref "C9") (pin "2") (pinfunction "2_2") (pintype "passive"))
      (node (ref "D4") (pin "2") (pinfunction "K_2") (pintype "passive"))
      (node (ref "R8") (pin "2") (pinfunction "2_2") (pintype "passive"))
      (node (ref "U13") (pin "7") (pinfunction "7_7") (pintype "passive"))
      (node (ref "U14") (pin "7") (pinfunction "7_7") (pintype "passive"))
    )
    (net (code "59") (name "Net-(R7-Pad2)") (class "Default")
      (node (ref "R7") (pin "2") (pinfunction "2_2") (pintype "passive"))
      (node (ref "U9") (pin "13") (pinfunction "13_13") (pintype "passive"))
    )
    (net (code "60") (name "Net-(U1-Pad10)") (class "Default")
      (node (ref "U1") (pin "10") (pinfunction "10_10") (pintype "passive"))
      (node (ref "U5") (pin "10") (pinfunction "10_10") (pintype "passive"))
    )
    (net (code "61") (name "Net-(U1-Pad11)") (class "Default")
      (node (ref "U1") (pin "11") (pinfunction "11_11") (pintype "passive"))
      (node (ref "U5") (pin "9") (pinfunction "9_9") (pintype "passive"))
    )
    (net (code "62") (name "Net-(U2A-CLKA)") (class "Default")
      (node (ref "U2") (pin "1") (pinfunction "CLKA_1") (pintype "input"))
      (node (ref "U2") (pin "6") (pinfunction "Q4A_6") (pintype "output"))
      (node (ref "U4") (pin "6") (pinfunction "D_6") (pintype "input"))
      (node (ref "U4") (pin "8") (pinfunction "E_8") (pintype "input"))
    )
    (net (code "63") (name "Net-(U3B-D)") (class "Default")
      (node (ref "U3") (pin "10") (pinfunction "L_10") (pintype "output"))
      (node (ref "U3") (pin "6") (pinfunction "D_6") (pintype "input"))
    )
    (net (code "64") (name "Net-(U3C-F)") (class "Default")
      (node (ref "D1") (pin "1") (pinfunction "1_1") (pintype "passive"))
      (node (ref "R2") (pin "1") (pinfunction "1_1") (pintype "passive"))
      (node (ref "U3") (pin "9") (pinfunction "F_9") (pintype "input"))
      (node (ref "U4") (pin "12") (pinfunction "G_12") (pintype "input"))
    )
    (net (code "65") (name "Net-(U4A-A)") (class "Default")
      (node (ref "U4") (pin "1") (pinfunction "A_1") (pintype "input"))
      (node (ref "U4") (pin "2") (pinfunction "B_2") (pintype "input"))
      (node (ref "U4") (pin "5") (pinfunction "C_5") (pintype "input"))
      (node (ref "U6") (pin "4") (pinfunction "Q2_A_4") (pintype "output"))
    )
    (net (code "66") (name "Net-(U7A-Q4_A)") (class "Default")
      (node (ref "U7") (pin "10") (pinfunction "Q4_A_10") (pintype "output"))
      (node (ref "U7") (pin "15") (pinfunction "DATA_B_15") (pintype "input"))
    )
    (net (code "67") (name "Net-(U8A-J)") (class "Default")
      (node (ref "R7") (pin "1") (pinfunction "1_1") (pintype "passive"))
      (node (ref "U8") (pin "3") (pinfunction "J_3") (pintype "output"))
    )
    (net (code "68") (name "Net-(U9-Pad2)") (class "Default")
      (node (ref "U9") (pin "2") (pinfunction "2_2") (pintype "passive"))
      (node (ref "U9") (pin "3") (pinfunction "3_3") (pintype "passive"))
    )
    (net (code "69") (name "Net-(U10A-Q3A)") (class "Default")
      (node (ref "U10") (pin "5") (pinfunction "Q3A_5") (pintype "output"))
      (node (ref "U12") (pin "5") (pinfunction "A2_5") (pintype "passive"))
    )
    (net (code "70") (name "Net-(U10A-Q4A)") (class "Default")
      (node (ref "U10") (pin "10") (pinfunction "ENB_10") (pintype "input"))
      (node (ref "U10") (pin "6") (pinfunction "Q4A_6") (pintype "output"))
    )
    (net (code "71") (name "Net-(U10B-Q2B)") (class "Default")
      (node (ref "U10") (pin "12") (pinfunction "Q2B_12") (pintype "output"))
      (node (ref "U12") (pin "7") (pinfunction "A1_7") (pintype "passive"))
      (node (ref "U8") (pin "8") (pinfunction "E_8") (pintype "input"))
    )
    (net (code "72") (name "Net-(U11-2)") (class "Default")
      (node (ref "U11") (pin "3") (pinfunction "2_3") (pintype "output"))
      (node (ref "U8") (pin "9") (pinfunction "F_9") (pintype "input"))
    )
    (net (code "73") (name "Net-(U11-3)") (class "Default")
      (node (ref "U11") (pin "15") (pinfunction "RST_15") (pintype "input"))
      (node (ref "U11") (pin "7") (pinfunction "3_7") (pintype "output"))
    )
    (net (code "74") (name "Net-(U12-S1)") (class "Default")
      (node (ref "U12") (pin "10") (pinfunction "S1_10") (pintype "passive"))
      (node (ref "U13") (pin "11") (pinfunction "11_11") (pintype "passive"))
      (node (ref "U14") (pin "11") (pinfunction "11_11") (pintype "passive"))
    )
    (net (code "75") (name "Net-(U12-S2)") (class "Default")
      (node (ref "U12") (pin "11") (pinfunction "S2_11") (pintype "passive"))
      (node (ref "U13") (pin "10") (pinfunction "10_10") (pintype "passive"))
      (node (ref "U14") (pin "10") (pinfunction "10_10") (pintype "passive"))
    )
    (net (code "76") (name "Net-(U12-S3)") (class "Default")
      (node (ref "U12") (pin "12") (pinfunction "S3_12") (pintype "passive"))
      (node (ref "U13") (pin "9") (pinfunction "9_9") (pintype "passive"))
      (node (ref "U14") (pin "9") (pinfunction "9_9") (pintype "passive"))
    )
    (net (code "77") (name "unconnected-(U2A-Q1A-Pad3)") (class "Default")
      (node (ref "U2") (pin "3") (pinfunction "Q1A_3") (pintype "output"))
    )
    (net (code "78") (name "unconnected-(U2A-Q2A-Pad4)") (class "Default")
      (node (ref "U2") (pin "4") (pinfunction "Q2A_4") (pintype "output"))
    )
    (net (code "79") (name "unconnected-(U2A-Q3A-Pad5)") (class "Default")
      (node (ref "U2") (pin "5") (pinfunction "Q3A_5") (pintype "output"))
    )
    (net (code "80") (name "unconnected-(U2B-Q1B-Pad11)") (class "Default")
      (node (ref "U2") (pin "11") (pinfunction "Q1B_11") (pintype "output"))
    )
    (net (code "81") (name "unconnected-(U2B-Q2B-Pad12)") (class "Default")
      (node (ref "U2") (pin "12") (pinfunction "Q2B_12") (pintype "output"))
    )
    (net (code "82") (name "unconnected-(U2B-Q3B-Pad13)") (class "Default")
      (node (ref "U2") (pin "13") (pinfunction "Q3B_13") (pintype "output"))
    )
    (net (code "83") (name "unconnected-(U2B-Q4B-Pad14)") (class "Default")
      (node (ref "U2") (pin "14") (pinfunction "Q4B_14") (pintype "output"))
    )
    (net (code "84") (name "unconnected-(U3A-J-Pad3)") (class "Default")
      (node (ref "U3") (pin "3") (pinfunction "J_3") (pintype "output+no_connect"))
    )
    (net (code "85") (name "unconnected-(U6A-Q1_A-Pad5)") (class "Default")
      (node (ref "U6") (pin "5") (pinfunction "Q1_A_5") (pintype "output"))
    )
    (net (code "86") (name "unconnected-(U6A-Q3_A-Pad3)") (class "Default")
      (node (ref "U6") (pin "3") (pinfunction "Q3_A_3") (pintype "output"))
    )
    (net (code "87") (name "unconnected-(U6A-Q4_A-Pad10)") (class "Default")
      (node (ref "U6") (pin "10") (pinfunction "Q4_A_10") (pintype "output"))
    )
    (net (code "88") (name "unconnected-(U6B-Q1_B-Pad13)") (class "Default")
      (node (ref "U6") (pin "13") (pinfunction "Q1_B_13") (pintype "output"))
    )
    (net (code "89") (name "unconnected-(U6B-Q3_B-Pad11)") (class "Default")
      (node (ref "U6") (pin "11") (pinfunction "Q3_B_11") (pintype "output"))
    )
    (net (code "90") (name "unconnected-(U6B-Q4_B-Pad2)") (class "Default")
      (node (ref "U6") (pin "2") (pinfunction "Q4_B_2") (pintype "output"))
    )
    (net (code "91") (name "unconnected-(U7A-Q1_A-Pad5)") (class "Default")
      (node (ref "U7") (pin "5") (pinfunction "Q1_A_5") (pintype "output"))
    )
    (net (code "92") (name "unconnected-(U7A-Q2_A-Pad4)") (class "Default")
      (node (ref "U7") (pin "4") (pinfunction "Q2_A_4") (pintype "output"))
    )
    (net (code "93") (name "unconnected-(U7A-Q3_A-Pad3)") (class "Default")
      (node (ref "U7") (pin "3") (pinfunction "Q3_A_3") (pintype "output"))
    )
    (net (code "94") (name "unconnected-(U7B-Q1_B-Pad13)") (class "Default")
      (node (ref "U7") (pin "13") (pinfunction "Q1_B_13") (pintype "output"))
    )
    (net (code "95") (name "unconnected-(U7B-Q2_B-Pad12)") (class "Default")
      (node (ref "U7") (pin "12") (pinfunction "Q2_B_12") (pintype "output"))
    )
    (net (code "96") (name "unconnected-(U7B-Q3_B-Pad11)") (class "Default")
      (node (ref "U7") (pin "11") (pinfunction "Q3_B_11") (pintype "output"))
    )
    (net (code "97") (name "unconnected-(U8B-K-Pad4)") (class "Default")
      (node (ref "U8") (pin "4") (pinfunction "K_4") (pintype "output+no_connect"))
    )
    (net (code "98") (name "unconnected-(U10B-Q1B-Pad11)") (class "Default")
      (node (ref "U10") (pin "11") (pinfunction "Q1B_11") (pintype "output"))
    )
    (net (code "99") (name "unconnected-(U11-0-Pad2)") (class "Default")
      (node (ref "U11") (pin "2") (pinfunction "0_2") (pintype "output"))
    )
    (net (code "100") (name "unconnected-(U11-4-Pad11)") (class "Default")
      (node (ref "U11") (pin "11") (pinfunction "4_11") (pintype "output"))
    )
    (net (code "101") (name "unconnected-(U11-5-Pad4)") (class "Default")
      (node (ref "U11") (pin "4") (pinfunction "5_4") (pintype "output"))
    )
    (net (code "102") (name "unconnected-(U11-6-Pad5)") (class "Default")
      (node (ref "U11") (pin "5") (pinfunction "6_5") (pintype "output"))
    )
    (net (code "103") (name "unconnected-(U11-7-Pad10)") (class "Default")
      (node (ref "U11") (pin "10") (pinfunction "7_10") (pintype "output"))
    )
    (net (code "104") (name "unconnected-(U11-CO-Pad12)") (class "Default")
      (node (ref "U11") (pin "12") (pinfunction "CO_12") (pintype "output"))
    )
    (net (code "105") (name "unconnected-(U11-Pad1)") (class "Default")
      (node (ref "U11") (pin "1") (pinfunction "1_1") (pintype "output"))
    )
    (net (code "106") (name "unconnected-(U12-COUT-Pad14)") (class "Default")
      (node (ref "U12") (pin "14") (pinfunction "COUT_14") (pintype "passive+no_connect"))
    )
    (net (code "107") (name "unconnected-(U12-S4-Pad13)") (class "Default")
      (node (ref "U12") (pin "13") (pinfunction "S4_13") (pintype "passive+no_connect"))
    )
  )
)
